# VUE_PIC32_v1_0_Signals.net
KiCad netlist of a schematic drawn in Altium Designer
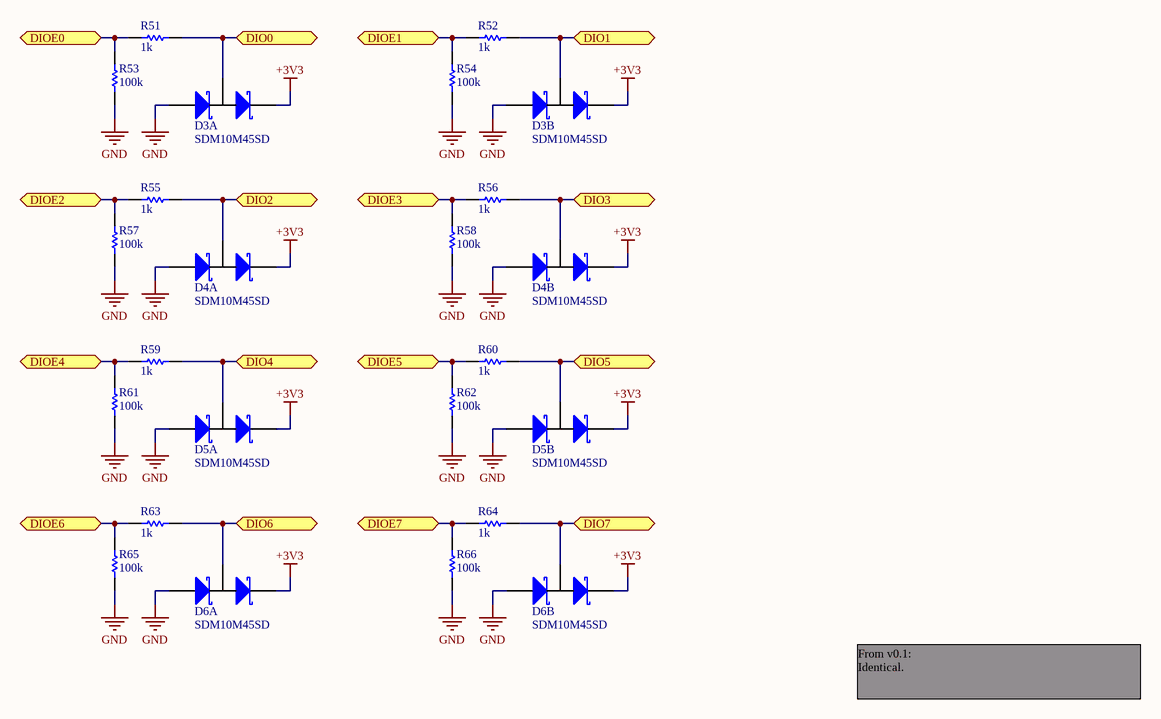
[diagram p0: VUE_PIC32_v1_0_Signals.SchDoc]

(export (version "E")
  (design (tool "Eeschema 10.0.6"))
  (components
    (comp (ref "D3")
      (value "SDM10M45SD")
      (footprint "SOT23-6")
      (description "DIODE SCHOTTKY ARRAY 45V SOT26")
      (fields (field (name "MFG") "Diodes Inc") (field (name "MFGPARTNUMBER") "SDM10M45SD-7-F"))
      (libsource (lib "JFD_Semi") (part "DIODE_DIODESINC_SDM10M45SD_QUAD_SCHOTTKY_45V_200MA"))
    )
    (comp (ref "D4")
      (value "SDM10M45SD")
      (footprint "SOT23-6")
      (description "DIODE SCHOTTKY ARRAY 45V SOT26")
      (fields (field (name "MFG") "Diodes Inc") (field (name "MFGPARTNUMBER") "SDM10M45SD-7-F"))
      (libsource (lib "JFD_Semi") (part "DIODE_DIODESINC_SDM10M45SD_QUAD_SCHOTTKY_45V_200MA"))
    )
    (comp (ref "D5")
      (value "SDM10M45SD")
      (footprint "SOT23-6")
      (description "DIODE SCHOTTKY ARRAY 45V SOT26")
      (fields (field (name "MFG") "Diodes Inc") (field (name "MFGPARTNUMBER") "SDM10M45SD-7-F"))
      (libsource (lib "JFD_Semi") (part "DIODE_DIODESINC_SDM10M45SD_QUAD_SCHOTTKY_45V_200MA"))
    )
    (comp (ref "D6")
      (value "SDM10M45SD")
      (footprint "SOT23-6")
      (description "DIODE SCHOTTKY ARRAY 45V SOT26")
      (fields (field (name "MFG") "Diodes Inc") (field (name "MFGPARTNUMBER") "SDM10M45SD-7-F"))
      (libsource (lib "JFD_Semi") (part "DIODE_DIODESINC_SDM10M45SD_QUAD_SCHOTTKY_45V_200MA"))
    )
    (comp (ref "R51")
      (value "1k")
      (footprint "0402")
      (description "RES 1.00K OHM 1/16W 1% 0402 SMD")
      (fields (field (name "MFG") "Yageo") (field (name "MFGPARTNUMBER") "RC0402FR-071KL"))
      (libsource (lib "JFD_Res") (part "RES_YAGEO_0402_1K_1PCT"))
    )
    (comp (ref "R52")
      (value "1k")
      (footprint "0402")
      (description "RES 1.00K OHM 1/16W 1% 0402 SMD")
      (fields (field (name "MFG") "Yageo") (field (name "MFGPARTNUMBER") "RC0402FR-071KL"))
      (libsource (lib "JFD_Res") (part "RES_YAGEO_0402_1K_1PCT"))
    )
    (comp (ref "R53")
      (value "100k")
      (footprint "0402")
      (description "RES 100K OHM 1/16W 1% 0402 SMD")
      (fields (field (name "MFG") "Yageo") (field (name "MFGPARTNUMBER") "RC0402FR-07100KL"))
      (libsource (lib "JFD_Res") (part "RES_YAGEO_0402_100K_1PCT"))
    )
    (comp (ref "R54")
      (value "100k")
      (footprint "0402")
      (description "RES 100K OHM 1/16W 1% 0402 SMD")
      (fields (field (name "MFG") "Yageo") (field (name "MFGPARTNUMBER") "RC0402FR-07100KL"))
      (libsource (lib "JFD_Res") (part "RES_YAGEO_0402_100K_1PCT"))
    )
    (comp (ref "R55")
      (value "1k")
      (footprint "0402")
      (description "RES 1.00K OHM 1/16W 1% 0402 SMD")
      (fields (field (name "MFG") "Yageo") (field (name "MFGPARTNUMBER") "RC0402FR-071KL"))
      (libsource (lib "JFD_Res") (part "RES_YAGEO_0402_1K_1PCT"))
    )
    (comp (ref "R56")
      (value "1k")
      (footprint "0402")
      (description "RES 1.00K OHM 1/16W 1% 0402 SMD")
      (fields (field (name "MFG") "Yageo") (field (name "MFGPARTNUMBER") "RC0402FR-071KL"))
      (libsource (lib "JFD_Res") (part "RES_YAGEO_0402_1K_1PCT"))
    )
    (comp (ref "R57")
      (value "100k")
      (footprint "0402")
      (description "RES 100K OHM 1/16W 1% 0402 SMD")
      (fields (field (name "MFG") "Yageo") (field (name "MFGPARTNUMBER") "RC0402FR-07100KL"))
      (libsource (lib "JFD_Res") (part "RES_YAGEO_0402_100K_1PCT"))
    )
    (comp (ref "R58")
      (value "100k")
      (footprint "0402")
      (description "RES 100K OHM 1/16W 1% 0402 SMD")
      (fields (field (name "MFG") "Yageo") (field (name "MFGPARTNUMBER") "RC0402FR-07100KL"))
      (libsource (lib "JFD_Res") (part "RES_YAGEO_0402_100K_1PCT"))
    )
    (comp (ref "R59")
      (value "1k")
      (footprint "0402")
      (description "RES 1.00K OHM 1/16W 1% 0402 SMD")
      (fields (field (name "MFG") "Yageo") (field (name "MFGPARTNUMBER") "RC0402FR-071KL"))
      (libsource (lib "JFD_Res") (part "RES_YAGEO_0402_1K_1PCT"))
    )
    (comp (ref "R60")
      (value "1k")
      (footprint "0402")
      (description "RES 1.00K OHM 1/16W 1% 0402 SMD")
      (fields (field (name "MFG") "Yageo") (field (name "MFGPARTNUMBER") "RC0402FR-071KL"))
      (libsource (lib "JFD_Res") (part "RES_YAGEO_0402_1K_1PCT"))
    )
    (comp (ref "R61")
      (value "100k")
      (footprint "0402")
      (description "RES 100K OHM 1/16W 1% 0402 SMD")
      (fields (field (name "MFG") "Yageo") (field (name "MFGPARTNUMBER") "RC0402FR-07100KL"))
      (libsource (lib "JFD_Res") (part "RES_YAGEO_0402_100K_1PCT"))
    )
    (comp (ref "R62")
      (value "100k")
      (footprint "0402")
      (description "RES 100K OHM 1/16W 1% 0402 SMD")
      (fields (field (name "MFG") "Yageo") (field (name "MFGPARTNUMBER") "RC0402FR-07100KL"))
      (libsource (lib "JFD_Res") (part "RES_YAGEO_0402_100K_1PCT"))
    )
    (comp (ref "R63")
      (value "1k")
      (footprint "0402")
      (description "RES 1.00K OHM 1/16W 1% 0402 SMD")
      (fields (field (name "MFG") "Yageo") (field (name "MFGPARTNUMBER") "RC0402FR-071KL"))
      (libsource (lib "JFD_Res") (part "RES_YAGEO_0402_1K_1PCT"))
    )
    (comp (ref "R64")
      (value "1k")
      (footprint "0402")
      (description "RES 1.00K OHM 1/16W 1% 0402 SMD")
      (fields (field (name "MFG") "Yageo") (field (name "MFGPARTNUMBER") "RC0402FR-071KL"))
      (libsource (lib "JFD_Res") (part "RES_YAGEO_0402_1K_1PCT"))
    )
    (comp (ref "R65")
      (value "100k")
      (footprint "0402")
      (description "RES 100K OHM 1/16W 1% 0402 SMD")
      (fields (field (name "MFG") "Yageo") (field (name "MFGPARTNUMBER") "RC0402FR-07100KL"))
      (libsource (lib "JFD_Res") (part "RES_YAGEO_0402_100K_1PCT"))
    )
    (comp (ref "R66")
      (value "100k")
      (footprint "0402")
      (description "RES 100K OHM 1/16W 1% 0402 SMD")
      (fields (field (name "MFG") "Yageo") (field (name "MFGPARTNUMBER") "RC0402FR-07100KL"))
      (libsource (lib "JFD_Res") (part "RES_YAGEO_0402_100K_1PCT"))
    )
  )
  (nets
    (net (code "1") (name "+3V3") (class "Default")
      (node (ref "D3") (pin "2") (pinfunction "K_2") (pintype "passive"))
      (node (ref "D3") (pin "5") (pinfunction "K_5") (pintype "passive"))
      (node (ref "D4") (pin "2") (pinfunction "K_2") (pintype "passive"))
      (node (ref "D4") (pin "5") (pinfunction "K_5") (pintype "passive"))
      (node (ref "D5") (pin "2") (pinfunction "K_2") (pintype "passive"))
      (node (ref "D5") (pin "5") (pinfunction "K_5") (pintype "passive"))
      (node (ref "D6") (pin "2") (pinfunction "K_2") (pintype "passive"))
      (node (ref "D6") (pin "5") (pinfunction "K_5") (pintype "passive"))
    )
    (net (code "2") (name "/DIO0") (class "Default")
      (node (ref "D3") (pin "6") (pinfunction "M_6") (pintype "passive"))
      (node (ref "R51") (pin "2") (pinfunction "2_2") (pintype "passive"))
    )
    (net (code "3") (name "/DIO1") (class "Default")
      (node (ref "D3") (pin "3") (pinfunction "M_3") (pintype "passive"))
      (node (ref "R52") (pin "2") (pinfunction "2_2") (pintype "passive"))
    )
    (net (code "4") (name "/DIO2") (class "Default")
      (node (ref "D4") (pin "6") (pinfunction "M_6") (pintype "passive"))
      (node (ref "R55") (pin "2") (pinfunction "2_2") (pintype "passive"))
    )
    (net (code "5") (name "/DIO3") (class "Default")
      (node (ref "D4") (pin "3") (pinfunction "M_3") (pintype "passive"))
      (node (ref "R56") (pin "2") (pinfunction "2_2") (pintype "passive"))
    )
    (net (code "6") (name "/DIO4") (class "Default")
      (node (ref "D5") (pin "6") (pinfunction "M_6") (pintype "passive"))
      (node (ref "R59") (pin "2") (pinfunction "2_2") (pintype "passive"))
    )
    (net (code "7") (name "/DIO5") (class "Default")
      (node (ref "D5") (pin "3") (pinfunction "M_3") (pintype "passive"))
      (node (ref "R60") (pin "2") (pinfunction "2_2") (pintype "passive"))
    )
    (net (code "8") (name "/DIO6") (class "Default")
      (node (ref "D6") (pin "6") (pinfunction "M_6") (pintype "passive"))
      (node (ref "R63") (pin "2") (pinfunction "2_2") (pintype "passive"))
    )
    (net (code "9") (name "/DIO7") (class "Default")
      (node (ref "D6") (pin "3") (pinfunction "M_3") (pintype "passive"))
      (node (ref "R64") (pin "2") (pinfunction "2_2") (pintype "passive"))
    )
    (net (code "10") (name "/DIOE0") (class "Default")
      (node (ref "R51") (pin "1") (pinfunction "1_1") (pintype "passive"))
      (node (ref "R53") (pin "2") (pinfunction "2_2") (pintype "passive"))
    )
    (net (code "11") (name "/DIOE1") (class "Default")
      (node (ref "R52") (pin "1") (pinfunction "1_1") (pintype "passive"))
      (node (ref "R54") (pin "2") (pinfunction "2_2") (pintype "passive"))
    )
    (net (code "12") (name "/DIOE2") (class "Default")
      (node (ref "R55") (pin "1") (pinfunction "1_1") (pintype "passive"))
      (node (ref "R57") (pin "2") (pinfunction "2_2") (pintype "passive"))
    )
    (net (code "13") (name "/DIOE3") (class "Default")
      (node (ref "R56") (pin "1") (pinfunction "1_1") (pintype "passive"))
      (node (ref "R58") (pin "2") (pinfunction "2_2") (pintype "passive"))
    )
    (net (code "14") (name "/DIOE4") (class "Default")
      (node (ref "R59") (pin "1") (pinfunction "1_1") (pintype "passive"))
      (node (ref "R61") (pin "2") (pinfunction "2_2") (pintype "passive"))
    )
    (net (code "15") (name "/DIOE5") (class "Default")
      (node (ref "R60") (pin "1") (pinfunction "1_1") (pintype "passive"))
      (node (ref "R62") (pin "2") (pinfunction "2_2") (pintype "passive"))
    )
    (net (code "16") (name "/DIOE6") (class "Default")
      (node (ref "R63") (pin "1") (pinfunction "1_1") (pintype "passive"))
      (node (ref "R65") (pin "2") (pinfunction "2_2") (pintype "passive"))
    )
    (net (code "17") (name "/DIOE7") (class "Default")
      (node (ref "R64") (pin "1") (pinfunction "1_1") (pintype "passive"))
      (node (ref "R66") (pin "2") (pinfunction "2_2") (pintype "passive"))
    )
    (net (code "18") (name "GND") (class "Default")
      (node (ref "D3") (pin "1") (pinfunction "A_1") (pintype "passive"))
      (node (ref "D3") (pin "4") (pinfunction "A_4") (pintype "passive"))
      (node (ref "D4") (pin "1") (pinfunction "A_1") (pintype "passive"))
      (node (ref "D4") (pin "4") (pinfunction "A_4") (pintype "passive"))
      (node (ref "D5") (pin "1") (pinfunction "A_1") (pintype "passive"))
      (node (ref "D5") (pin "4") (pinfunction "A_4") (pintype "passive"))
      (node (ref "D6") (pin "1") (pinfunction "A_1") (pintype "passive"))
      (node (ref "D6") (pin "4") (pinfunction "A_4") (pintype "passive"))
      (node (ref "R53") (pin "1") (pinfunction "1_1") (pintype "passive"))
      (node (ref "R54") (pin "1") (pinfunction "1_1") (pintype "passive"))
      (node (ref "R57") (pin "1") (pinfunction "1_1") (pintype "passive"))
      (node (ref "R58") (pin "1") (pinfunction "1_1") (pintype "passive"))
      (node (ref "R61") (pin "1") (pinfunction "1_1") (pintype "passive"))
      (node (ref "R62") (pin "1") (pinfunction "1_1") (pintype "passive"))
      (node (ref "R65") (pin "1") (pinfunction "1_1") (pintype "passive"))
      (node (ref "R66") (pin "1") (pinfunction "1_1") (pintype "passive"))
    )
  )
)
